# ECE445-Transmitter-Schematic-V-Converter.net
KiCad netlist of a schematic drawn in EAGLE
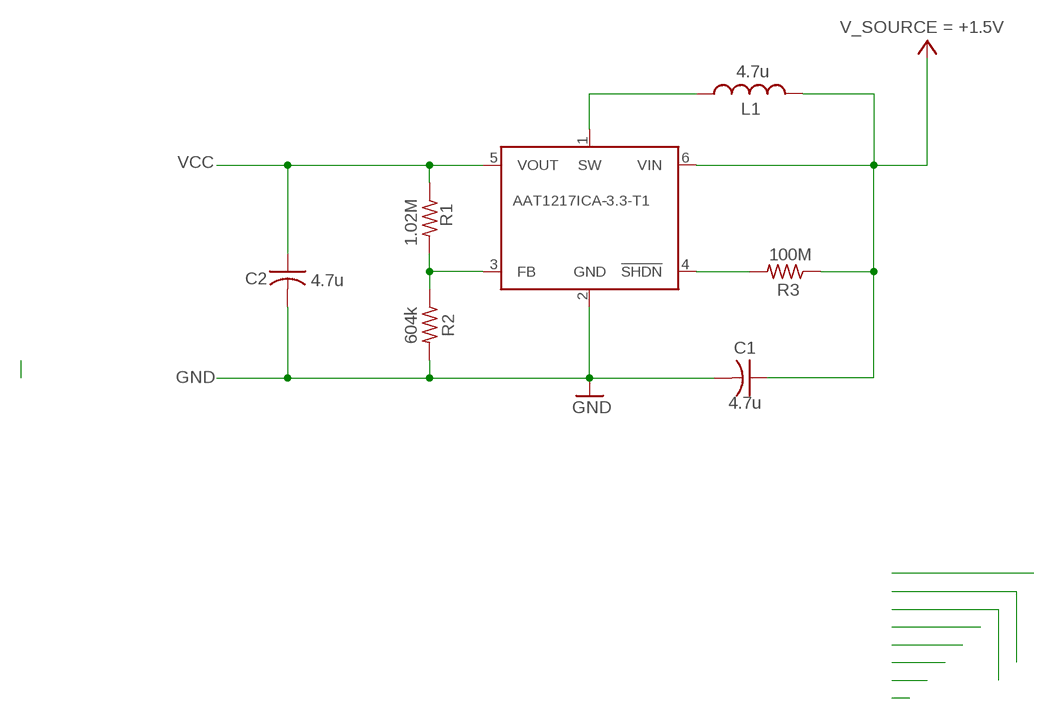
[diagram p0: schematic, sheet 1]

(export (version "E")
  (design (tool "Eeschema 10.0.6"))
  (components
    (comp (ref "-")
      (value "AAT1217ICA-3.3-T1")
      (footprint "eagle-import:TSOT-23-6")
      (libsource (lib "eagle-import") (part "AAT1217ICA-3.3-T1"))
    )
    (comp (ref "C1")
      (value "4.7u")
      (footprint "eagle-import:C025-024X044")
      (libsource (lib "eagle-import") (part "C-US025-024X044"))
    )
    (comp (ref "C2")
      (value "4.7u")
      (footprint "eagle-import:C025-024X044")
      (libsource (lib "eagle-import") (part "C-US025-024X044"))
    )
    (comp (ref "L1")
      (value "4.7u")
      (footprint "eagle-import:0204_5")
      (libsource (lib "eagle-import") (part "L-US0204/5"))
    )
    (comp (ref "R1")
      (value "1.02M")
      (footprint "eagle-import:0204V")
      (libsource (lib "eagle-import") (part "R-US_0204/2V"))
    )
    (comp (ref "R2")
      (value "604k")
      (footprint "eagle-import:0204V")
      (libsource (lib "eagle-import") (part "R-US_0204/2V"))
    )
    (comp (ref "R3")
      (value "100M")
      (footprint "eagle-import:0204V")
      (libsource (lib "eagle-import") (part "R-US_0204/2V"))
    )
  )
  (nets
    (net (code "1") (name "/VCC") (class "Default")
      (node (ref "-") (pin "5") (pinfunction "VOUT_5") (pintype "bidirectional"))
      (node (ref "C2") (pin "1") (pinfunction "1_1") (pintype "passive"))
      (node (ref "R1") (pin "1") (pinfunction "1_1") (pintype "passive"))
    )
    (net (code "2") (name "GND") (class "Default")
      (node (ref "-") (pin "2") (pinfunction "GND_2") (pintype "bidirectional"))
      (node (ref "C1") (pin "2") (pinfunction "2_2") (pintype "passive"))
      (node (ref "C2") (pin "2") (pinfunction "2_2") (pintype "passive"))
      (node (ref "R2") (pin "2") (pinfunction "2_2") (pintype "passive"))
    )
    (net (code "3") (name "Net-(--FB)") (class "Default")
      (node (ref "-") (pin "3") (pinfunction "FB_3") (pintype "bidirectional"))
      (node (ref "R1") (pin "2") (pinfunction "2_2") (pintype "passive"))
      (node (ref "R2") (pin "1") (pinfunction "1_1") (pintype "passive"))
    )
    (net (code "4") (name "Net-(--SW)") (class "Default")
      (node (ref "-") (pin "1") (pinfunction "SW_1") (pintype "bidirectional"))
      (node (ref "L1") (pin "1") (pinfunction "1_1") (pintype "passive"))
    )
    (net (code "5") (name "Net-(--~{SHDN})") (class "Default")
      (node (ref "-") (pin "4") (pinfunction "~{SHDN}_4") (pintype "bidirectional"))
      (node (ref "R3") (pin "2") (pinfunction "2_2") (pintype "passive"))
    )
    (net (code "6") (name "V_SOURCE = +1.5V") (class "Default")
      (node (ref "-") (pin "6") (pinfunction "VIN_6") (pintype "bidirectional"))
      (node (ref "C1") (pin "1") (pinfunction "1_1") (pintype "passive"))
      (node (ref "L1") (pin "2") (pinfunction "2_2") (pintype "passive"))
      (node (ref "R3") (pin "1") (pinfunction "1_1") (pintype "passive"))
    )
  )
)
